# Sensor_Board.net
KiCad netlist of a schematic drawn in Altium Designer
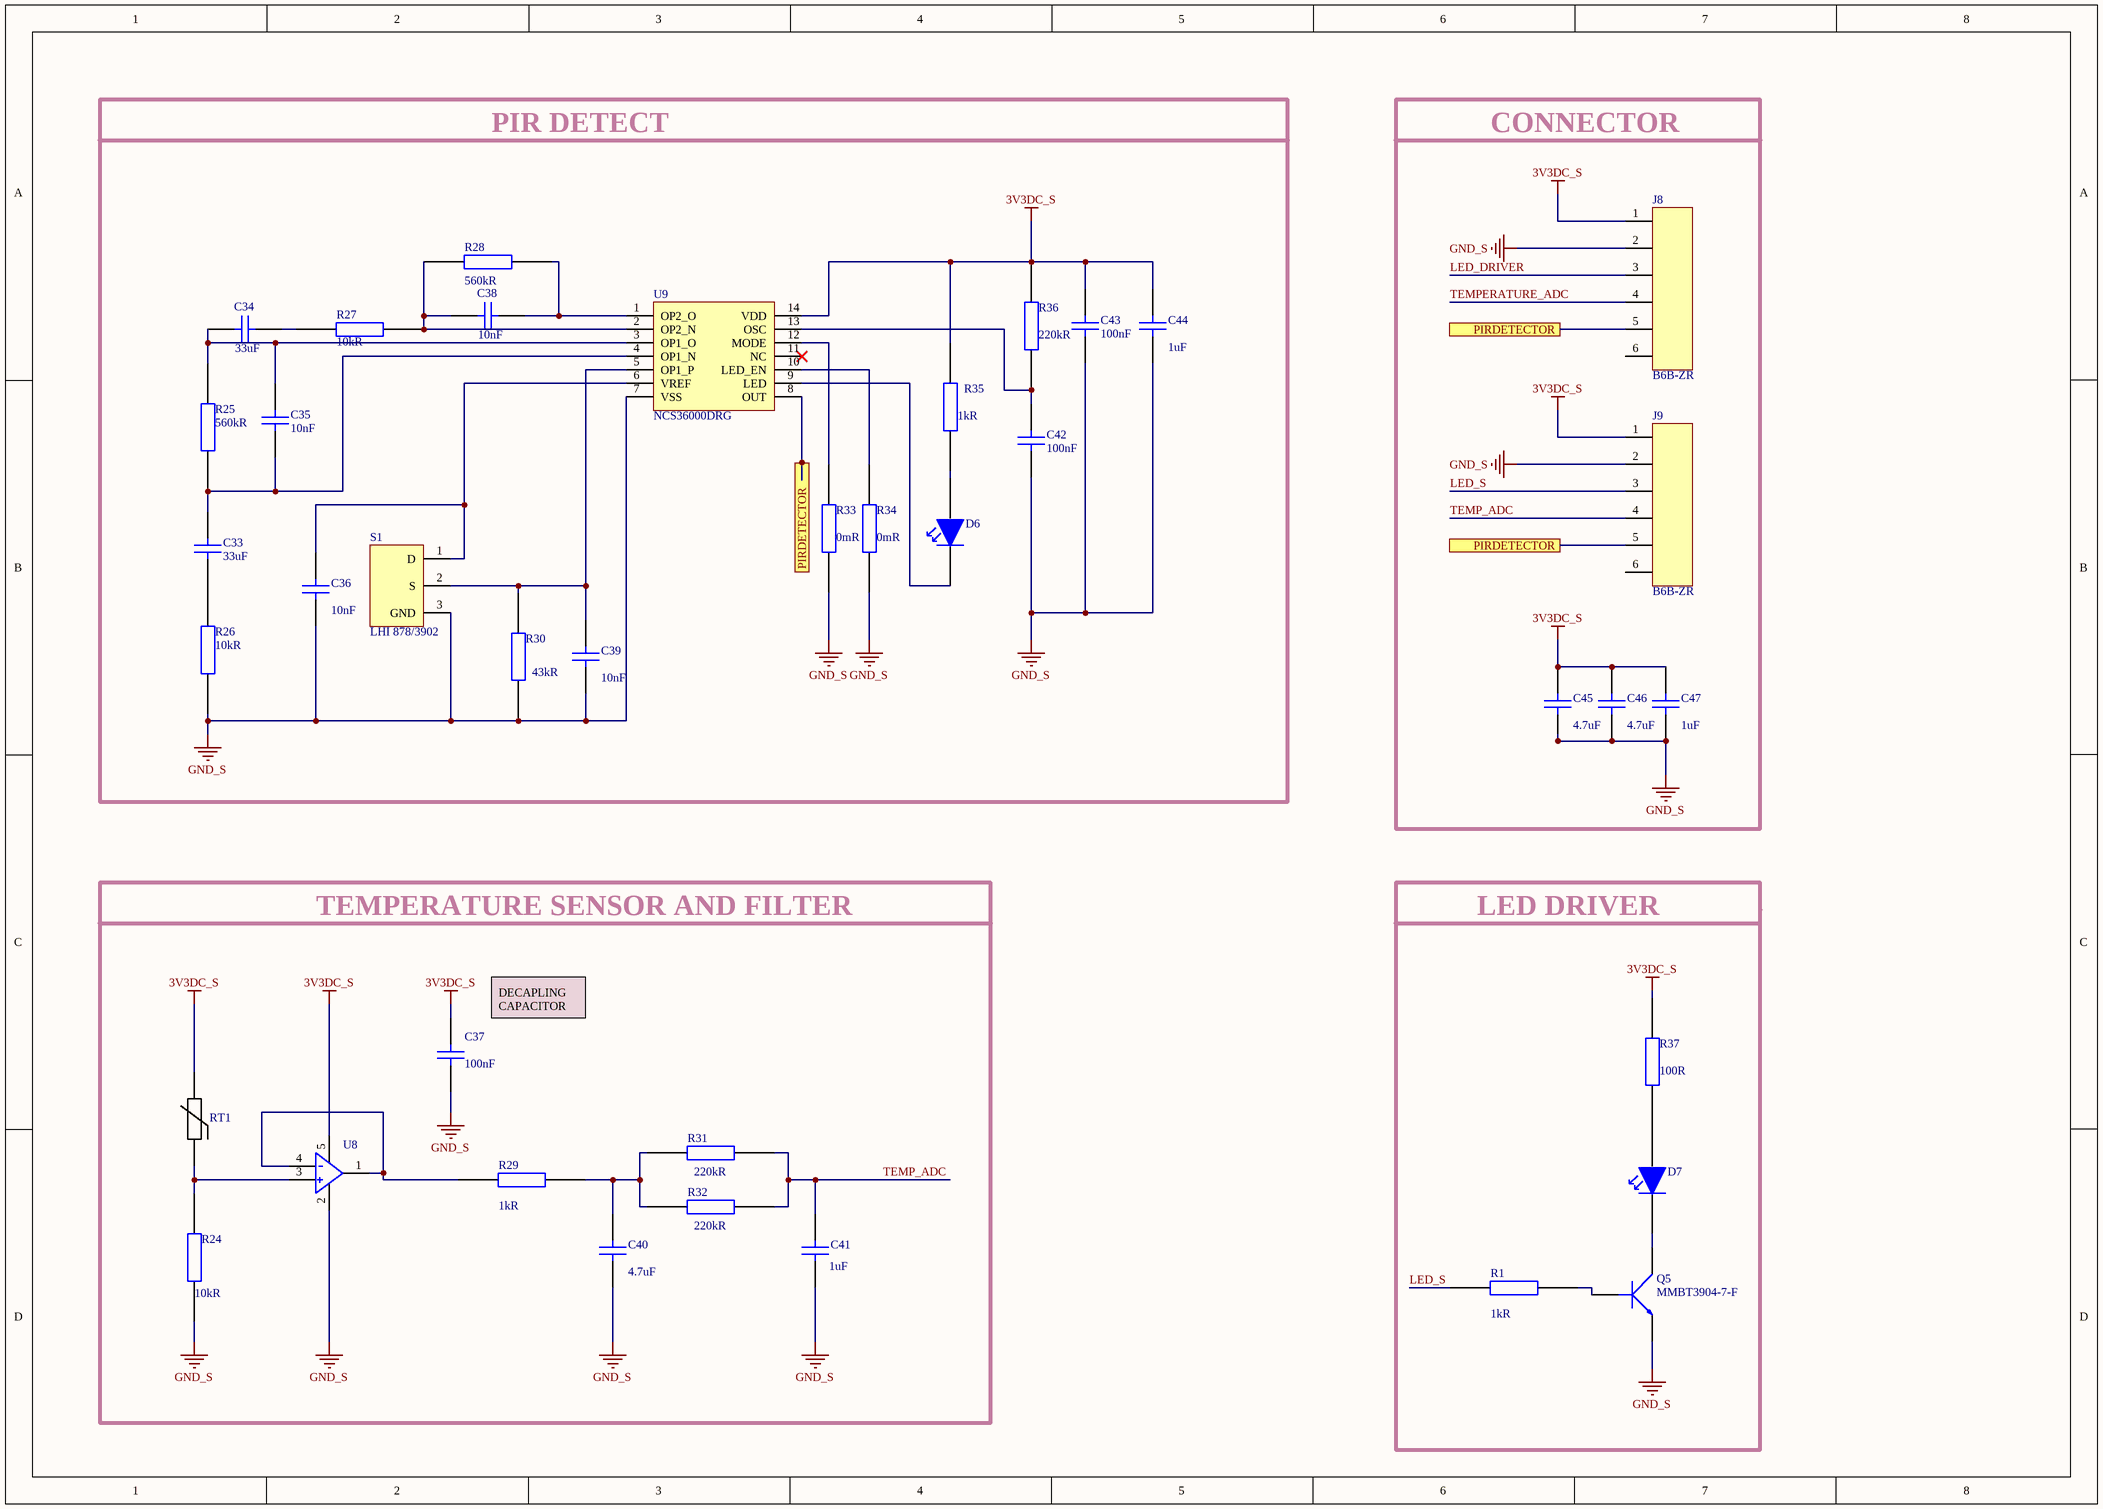
[diagram p0: Sensor Board.SchDoc]

(export (version "E")
  (design (tool "Eeschema 10.0.6"))
  (components
    (comp (ref "C33")
      (value "33uF")
      (footprint "CAP_1206")
      (description "Multilayer Ceramic Capacitor, 33 uF, 25 V, ± 20%, 1206")
      (fields
        (field (name "MANUFACTURER") "TDK")
        (field (name "MANUFACTURER PART NUMBER") "C3216X5R1E336M160AC")
        (field (name "DESIGNED BY") "Selenay")
      )
      (libsource (lib "LIBRARY1") (part "CAP CER 33uF 1206"))
    )
    (comp (ref "C34")
      (value "33uF")
      (footprint "CAP_1206")
      (description "Multilayer Ceramic Capacitor, 33 uF, 25 V, ± 20%, 1206")
      (fields
        (field (name "MANUFACTURER") "TDK")
        (field (name "MANUFACTURER PART NUMBER") "C3216X5R1E336M160AC")
        (field (name "DESIGNED BY") "Selenay")
      )
      (libsource (lib "LIBRARY1") (part "CAP CER 33uF 1206"))
    )
    (comp (ref "C35")
      (value "0603B103K160CT")
      (footprint "CAP_0603")
      (description "0603 16V X7R .01uF 10% multilayer ceramic capacitor")
      (fields
        (field (name "MANUFACTURER") "Walsin Technologies")
        (field (name "VALUES") "10nF")
        (field (name "DESIGNED BY") "Selenay")
      )
      (libsource (lib "LIBRARY1") (part "CAP CER 10nF 0603"))
    )
    (comp (ref "C36")
      (value "0603B103K160CT")
      (footprint "CAP_0603")
      (description "0603 16V X7R .01uF 10% multilayer ceramic capacitor")
      (fields
        (field (name "MANUFACTURER") "Walsin Technologies")
        (field (name "VALUES") "10nF")
        (field (name "DESIGNED BY") "Selenay")
      )
      (libsource (lib "LIBRARY1") (part "CAP CER 10nF 0603"))
    )
    (comp (ref "C37")
      (value "100nF")
      (footprint "CAP_0603")
      (description "Multilayer Ceramic Capacitor, 0.1 uF, 50 V, ± 10%, X7R, 0603 [1608 Metric]")
      (fields
        (field (name "MANUFACTURER") "KEMET")
        (field (name "MANUFACTURER PART NUMBER") "C0603C104K5RACTU")
        (field (name "DESIGNED BY") "Selenay")
      )
      (libsource (lib "LIBRARY1") (part "CAP CER 100nF 0603"))
    )
    (comp (ref "C38")
      (value "0603B103K160CT")
      (footprint "CAP_0603")
      (description "0603 16V X7R .01uF 10% multilayer ceramic capacitor")
      (fields
        (field (name "MANUFACTURER") "Walsin Technologies")
        (field (name "VALUES") "10nF")
        (field (name "DESIGNED BY") "Selenay")
      )
      (libsource (lib "LIBRARY1") (part "CAP CER 10nF 0603"))
    )
    (comp (ref "C39")
      (value "0603B103K160CT")
      (footprint "CAP_0603")
      (description "0603 16V X7R .01uF 10% multilayer ceramic capacitor")
      (fields
        (field (name "MANUFACTURER") "Walsin Technologies")
        (field (name "VALUES") "10nF")
        (field (name "DESIGNED BY") "Selenay")
      )
      (libsource (lib "LIBRARY1") (part "CAP CER 10nF 0603"))
    )
    (comp (ref "C40")
      (value "4.7uF")
      (footprint "CAP_0805")
      (description "Multilayer Ceramic Capacitor, 4.7 uF, 25 V, ± 10%")
      (fields
        (field (name "MANUFACTURER") "Samsung")
        (field (name "MANUFACTURER PART NUMBER") "CL21A475KAQNNNE")
        (field (name "DESIGNED BY") "Selenay")
      )
      (libsource (lib "LIBRARY1") (part "CAP CER 4.7uF 0805"))
    )
    (comp (ref "C41")
      (value "1uF")
      (footprint "CAP_0805")
      (description "Multilayer Ceramic Capacitor, 1 uF, 50 V, ± 10%, X7R, 0805 [2012 Metric]")
      (fields
        (field (name "MANUFACTURER") "Samsung")
        (field (name "MANUFACTURER PART NUMBER") "CL21B105KBFNNNE")
        (field (name "DESIGNED BY") "Selenay")
      )
      (libsource (lib "LIBRARY1") (part "CAP CER 1uF 0805"))
    )
    (comp (ref "C42")
      (value "100nF")
      (footprint "CAP_0603")
      (description "Multilayer Ceramic Capacitor, 0.1 uF, 50 V, ± 10%, X7R, 0603 [1608 Metric]")
      (fields
        (field (name "MANUFACTURER") "KEMET")
        (field (name "MANUFACTURER PART NUMBER") "C0603C104K5RACTU")
        (field (name "DESIGNED BY") "Selenay")
      )
      (libsource (lib "LIBRARY1") (part "CAP CER 100nF 0603"))
    )
    (comp (ref "C43")
      (value "100nF")
      (footprint "CAP_0603")
      (description "Multilayer Ceramic Capacitor, 0.1 uF, 50 V, ± 10%, X7R, 0603 [1608 Metric]")
      (fields
        (field (name "MANUFACTURER") "KEMET")
        (field (name "MANUFACTURER PART NUMBER") "C0603C104K5RACTU")
        (field (name "DESIGNED BY") "Selenay")
      )
      (libsource (lib "LIBRARY1") (part "CAP CER 100nF 0603"))
    )
    (comp (ref "C44")
      (value "1uF")
      (footprint "CAP_0805")
      (description "Multilayer Ceramic Capacitor, 1 uF, 50 V, ± 10%, X7R, 0805 [2012 Metric]")
      (fields
        (field (name "MANUFACTURER") "Samsung")
        (field (name "MANUFACTURER PART NUMBER") "CL21B105KBFNNNE")
        (field (name "DESIGNED BY") "Selenay")
      )
      (libsource (lib "LIBRARY1") (part "CAP CER 1uF 0805"))
    )
    (comp (ref "C45")
      (value "4.7uF")
      (footprint "CAP_0805")
      (description "Multilayer Ceramic Capacitor, 4.7 uF, 25 V, ± 10%")
      (fields
        (field (name "MANUFACTURER") "Samsung")
        (field (name "MANUFACTURER PART NUMBER") "CL21A475KAQNNNE")
        (field (name "DESIGNED BY") "Selenay")
      )
      (libsource (lib "LIBRARY1") (part "CAP CER 4.7uF 0805"))
    )
    (comp (ref "C46")
      (value "4.7uF")
      (footprint "CAP_0805")
      (description "Multilayer Ceramic Capacitor, 4.7 uF, 25 V, ± 10%")
      (fields
        (field (name "MANUFACTURER") "Samsung")
        (field (name "MANUFACTURER PART NUMBER") "CL21A475KAQNNNE")
        (field (name "DESIGNED BY") "Selenay")
      )
      (libsource (lib "LIBRARY1") (part "CAP CER 4.7uF 0805"))
    )
    (comp (ref "C47")
      (value "1uF")
      (footprint "CAP_0805")
      (description "Multilayer Ceramic Capacitor, 1 uF, 50 V, ± 10%, X7R, 0805 [2012 Metric]")
      (fields
        (field (name "MANUFACTURER") "Samsung")
        (field (name "MANUFACTURER PART NUMBER") "CL21B105KBFNNNE")
        (field (name "DESIGNED BY") "Selenay")
      )
      (libsource (lib "LIBRARY1") (part "CAP CER 1uF 0805"))
    )
    (comp (ref "D6")
      (value "LTST-C171GKT")
      (footprint "LED_GREEN_0805")
      (description "LED Low-Power Uni-Color Green 565nm 2.1V 2-Pin Chip LED T/R")
      (fields (field (name "MANUFACTURER") "Vishay Lite-On"))
      (libsource (lib "LIBRARY1") (part "LED GREEN 0805"))
    )
    (comp (ref "D7")
      (value "LH R974-LP-1-0-20-R18")
      (footprint "LED_RED_0805")
      (fields (field (name "DESIGNED BY") "Selenay"))
      (libsource (lib "LIBRARY1") (part "LED RED 0805"))
    )
    (comp (ref "J8")
      (value "B6B-ZR")
      (footprint "B6B-ZR")
      (description "Conn Shrouded Header (4 Sides) HDR 6 POS 1.5mm Solder ST Top Entry SMD T/R")
      (fields
        (field (name "MANUFACTURER") "Wurth Electronics")
        (field (name "MANUFACTURER PART NUMBER") "64800611622")
      )
      (libsource (lib "LIBRARY1") (part "64800611622_CONN_6PIN"))
    )
    (comp (ref "J9")
      (value "B6B-ZR")
      (footprint "B6B-ZR")
      (description "Conn Shrouded Header (4 Sides) HDR 6 POS 1.5mm Solder ST Top Entry SMD T/R")
      (fields
        (field (name "MANUFACTURER") "Wurth Electronics")
        (field (name "MANUFACTURER PART NUMBER") "64800611622")
      )
      (libsource (lib "LIBRARY1") (part "64800611622_CONN_6PIN"))
    )
    (comp (ref "Q5")
      (value "MMBT3904-7-F")
      (footprint "SOT-23F")
      (description "Transistor General Purpose BJT NPN 40 Volt 0.2A Automotive 3-Pin SOT-23")
      (fields (field (name "MANUFACTURER") "Diodes Zetex") (field (name "DESIGNED BY") "Selenay"))
      (libsource (lib "LIBRARY1") (part "MMBT3904-7-F"))
    )
    (comp (ref "R1")
      (value "1kR")
      (footprint "RES_0603")
      (description "SMD Chip Resistor, 1 kOhm, ± 1%, 100 mW, 0603 [1608 Metric], Thick Film, General Purpose")
      (fields
        (field (name "MANUFACTURER") "Yageo")
        (field (name "MANUFACTURER PART NUMBER") "RC0603FR-071KL")
        (field (name "DESIGNED BY") "Selenay")
      )
      (libsource (lib "LIBRARY1") (part "RES 1K OHM 0603"))
    )
    (comp (ref "R24")
      (value "10kR")
      (footprint "RES_0603")
      (description "Res Thick Film 0603 10K Ohm 5% 1/10W ±100ppm/°C Molded SMD SMD Paper T/R")
      (fields
        (field (name "MANUFACTURER") "Stackpole Electronics")
        (field (name "MANUFACTURER PART NUMBER") "RMCF0603JT10K0")
        (field (name "DESIGNED BY") "Selenay")
      )
      (libsource (lib "LIBRARY1") (part "RES 10K OHM 0603"))
    )
    (comp (ref "R25")
      (value "560kR")
      (footprint "RES_0603")
      (description "SMD Chip Resistor, 560 kOhm, ± 5%, 100 mW, 0603 [1608 Metric], Thick Film, General Purpose")
      (fields
        (field (name "MANUFACTURER") "Yageo")
        (field (name "MANUFACTURER PART NUMBER") "RC0603JR-07560KL")
        (field (name "DESIGNED BY") "Selenay")
      )
      (libsource (lib "LIBRARY1") (part "RES 560K OHM 0603"))
    )
    (comp (ref "R26")
      (value "10kR")
      (footprint "RES_0603")
      (description "Res Thick Film 0603 10K Ohm 5% 1/10W ±100ppm/°C Molded SMD SMD Paper T/R")
      (fields
        (field (name "MANUFACTURER") "Stackpole Electronics")
        (field (name "MANUFACTURER PART NUMBER") "RMCF0603JT10K0")
        (field (name "DESIGNED BY") "Selenay")
      )
      (libsource (lib "") (part "RES 10K OHM 0603_1"))
    )
    (comp (ref "R27")
      (value "10kR")
      (footprint "RES_0603")
      (description "Res Thick Film 0603 10K Ohm 5% 1/10W ±100ppm/°C Molded SMD SMD Paper T/R")
      (fields
        (field (name "MANUFACTURER") "Stackpole Electronics")
        (field (name "MANUFACTURER PART NUMBER") "RMCF0603JT10K0")
        (field (name "DESIGNED BY") "Selenay")
      )
      (libsource (lib "") (part "RES 10K OHM 0603_2"))
    )
    (comp (ref "R28")
      (value "560kR")
      (footprint "RES_0603")
      (description "SMD Chip Resistor, 560 kOhm, ± 5%, 100 mW, 0603 [1608 Metric], Thick Film, General Purpose")
      (fields
        (field (name "MANUFACTURER") "Yageo")
        (field (name "MANUFACTURER PART NUMBER") "RC0603JR-07560KL")
        (field (name "DESIGNED BY") "Selenay")
      )
      (libsource (lib "") (part "RES 560K OHM 0603_1"))
    )
    (comp (ref "R29")
      (value "1kR")
      (footprint "RES_0603")
      (description "SMD Chip Resistor, 1 kOhm, ± 1%, 100 mW, 0603 [1608 Metric], Thick Film, General Purpose")
      (fields
        (field (name "MANUFACTURER") "Yageo")
        (field (name "MANUFACTURER PART NUMBER") "RC0603FR-071KL")
        (field (name "DESIGNED BY") "Selenay")
      )
      (libsource (lib "LIBRARY1") (part "RES 1K OHM 0603"))
    )
    (comp (ref "R30")
      (value "RC0603JR-0743KL")
      (footprint "RES_0603")
      (description "Res Thick Film 0603 43K Ohm 5% 0.1W(1/10W)")
      (fields
        (field (name "MANUFACTURER") "Yageo")
        (field (name "VALUES") "43kR")
        (field (name "DESIGNED BY") "Selenay")
      )
      (libsource (lib "LIBRARY1") (part "RES 43K OHM 0603"))
    )
    (comp (ref "R31")
      (value "RC0603JR-07220KL")
      (footprint "RES_0603")
      (description "SMD Chip Resistor, 220 kOhm, ± 5%, 100 mW, 0603")
      (fields
        (field (name "MANUFACTURER") "Yageo")
        (field (name "VALUES") "220kR")
        (field (name "DESIGNED BY") "Selenay")
      )
      (libsource (lib "LIBRARY1") (part "RES 220K OHM 0603"))
    )
    (comp (ref "R32")
      (value "RC0603JR-07220KL")
      (footprint "RES_0603")
      (description "SMD Chip Resistor, 220 kOhm, ± 5%, 100 mW, 0603")
      (fields
        (field (name "MANUFACTURER") "Yageo")
        (field (name "VALUES") "220kR")
        (field (name "DESIGNED BY") "Selenay")
      )
      (libsource (lib "LIBRARY1") (part "RES 220K OHM 0603"))
    )
    (comp (ref "R33")
      (value "0mR")
      (footprint "RES_0603")
      (description "GENERAL PURPOSE CHIP RESISTOR Metal Glaze/thick Film, 0.1W, 0ohm, Surface Mount, 0603")
      (fields
        (field (name "MANUFACTURER") "Yageo")
        (field (name "MANUFACTURER PART NUMBER") "RC0603JR-070RL")
        (field (name "DESIGNED BY") "Selenay")
      )
      (libsource (lib "LIBRARY1") (part "RES 0 OHM 0603"))
    )
    (comp (ref "R34")
      (value "0mR")
      (footprint "RES_0603")
      (description "GENERAL PURPOSE CHIP RESISTOR Metal Glaze/thick Film, 0.1W, 0ohm, Surface Mount, 0603")
      (fields
        (field (name "MANUFACTURER") "Yageo")
        (field (name "MANUFACTURER PART NUMBER") "RC0603JR-070RL")
        (field (name "DESIGNED BY") "Selenay")
      )
      (libsource (lib "LIBRARY1") (part "RES 0 OHM 0603"))
    )
    (comp (ref "R35")
      (value "1kR")
      (footprint "RES_0603")
      (description "SMD Chip Resistor, 1 kOhm, ± 1%, 100 mW, 0603 [1608 Metric], Thick Film, General Purpose")
      (fields
        (field (name "MANUFACTURER") "Yageo")
        (field (name "MANUFACTURER PART NUMBER") "RC0603FR-071KL")
        (field (name "DESIGNED BY") "Selenay")
      )
      (libsource (lib "") (part "RES 1K OHM 0603_1"))
    )
    (comp (ref "R36")
      (value "RC0603JR-07220KL")
      (footprint "RES_0603")
      (description "SMD Chip Resistor, 220 kOhm, ± 5%, 100 mW, 0603")
      (fields
        (field (name "MANUFACTURER") "Yageo")
        (field (name "VALUES") "220kR")
        (field (name "DESIGNED BY") "Selenay")
      )
      (libsource (lib "") (part "RES 220K OHM 0603_1"))
    )
    (comp (ref "R37")
      (value "100R")
      (footprint "RES_0603")
      (description "SMD Chip Resistor, 100 Ohm, ± 1%, 100 mW, 0603")
      (fields
        (field (name "MANUFACTURER") "Yageo")
        (field (name "MANUFACTURER PART NUMBER") "RC0603FR-07100RL")
        (field (name "DESIGNED BY") "Selenay")
      )
      (libsource (lib "LIBRARY1") (part "RES 100 OHM 0603"))
    )
    (comp (ref "RT1")
      (value "TFPT1206L1002FM")
      (footprint "RES_1206")
      (description "Thermistor PTC 10K Ohm 1% 2-Pin 1206 Surface Mount Solder Pad T/R Automotive")
      (fields
        (field (name "MANUFACTURER") "Vishay Dale")
        (field (name "TOLERANCE") "1%")
        (field (name "DESIGNED BY") "Selenay")
      )
      (libsource (lib "LIBRARY1") (part "TFPT1206L1002FM"))
    )
    (comp (ref "S1")
      (value "LHI 878/3902")
      (footprint "LHI 878")
      (description "SENSOR PYRO DETECTOR DUAL MOTION")
      (fields (field (name "DESIGNED BY") "Selenay"))
      (libsource (lib "LIBRARY1") (part "LHI 878/3902"))
    )
    (comp (ref "U8")
      (value "OPA314AIDBVR")
      (footprint "SOT23_5")
      (description "IC OPAMP GP 3MHZ RRO SOT23-5")
      (fields (field (name "MANUFACTURER") "Texas Instruments") (field (name "DESIGNED BY") "Selenay"))
      (libsource (lib "LIBRARY1") (part "OPA314"))
    )
    (comp (ref "U9")
      (value "NCS36000DRG")
      (footprint "SOIC14")
      (description "PIR CONTROLLER  NCS36000 Series Single 5.75V Passive Infrared Detector Controller (PIR) -SOIC-14")
      (fields (field (name "MANUFACTURER") "ON Semiconductor") (field (name "DESIGNED BY") "Selenay"))
      (libsource (lib "LIBRARY1") (part "NCS36000"))
    )
  )
  (nets
    (net (code "1") (name "/LED_DRIVER") (class "Default") (node (ref "J8") (pin "3") (pintype "passive")))
    (net (code "2") (name "/LED_S") (class "Default")
      (node (ref "J9") (pin "3") (pintype "passive"))
      (node (ref "R1") (pin "1") (pinfunction "1_1") (pintype "passive"))
    )
    (net (code "3") (name "/PIRDETECTOR") (class "Default")
      (node (ref "J8") (pin "5") (pintype "passive"))
      (node (ref "J9") (pin "5") (pintype "passive"))
      (node (ref "U9") (pin "8") (pinfunction "OUT_8") (pintype "passive"))
    )
    (net (code "4") (name "/TEMPERATURE_ADC") (class "Default")
      (node (ref "J8") (pin "4") (pintype "passive"))
    )
    (net (code "5") (name "/TEMP_ADC") (class "Default")
      (node (ref "C41") (pin "1") (pinfunction "1_1") (pintype "passive"))
      (node (ref "J9") (pin "4") (pintype "passive"))
      (node (ref "R31") (pin "2") (pinfunction "1_2") (pintype "passive"))
      (node (ref "R32") (pin "2") (pinfunction "1_2") (pintype "passive"))
    )
    (net (code "6") (name "3V3DC_S") (class "Default")
      (node (ref "C37") (pin "2") (pinfunction "2_2") (pintype "passive"))
      (node (ref "C43") (pin "2") (pinfunction "2_2") (pintype "passive"))
      (node (ref "C44") (pin "2") (pinfunction "2_2") (pintype "passive"))
      (node (ref "C45") (pin "2") (pinfunction "2_2") (pintype "passive"))
      (node (ref "C46") (pin "2") (pinfunction "2_2") (pintype "passive"))
      (node (ref "C47") (pin "2") (pinfunction "2_2") (pintype "passive"))
      (node (ref "J8") (pin "1") (pintype "passive"))
      (node (ref "J9") (pin "1") (pintype "passive"))
      (node (ref "R35") (pin "2") (pinfunction "1_2") (pintype "passive"))
      (node (ref "R36") (pin "1") (pinfunction "1_1") (pintype "passive"))
      (node (ref "R37") (pin "2") (pinfunction "1_2") (pintype "passive"))
      (node (ref "RT1") (pin "2") (pinfunction "2_2") (pintype "passive"))
      (node (ref "U8") (pin "5") (pintype "passive"))
      (node (ref "U9") (pin "14") (pinfunction "VDD_14") (pintype "passive"))
    )
    (net (code "7") (name "GND_S") (class "Default")
      (node (ref "C36") (pin "1") (pinfunction "1_1") (pintype "passive"))
      (node (ref "C37") (pin "1") (pinfunction "1_1") (pintype "passive"))
      (node (ref "C39") (pin "1") (pinfunction "1_1") (pintype "passive"))
      (node (ref "C40") (pin "1") (pinfunction "1_1") (pintype "passive"))
      (node (ref "C41") (pin "2") (pinfunction "2_2") (pintype "passive"))
      (node (ref "C42") (pin "1") (pinfunction "1_1") (pintype "passive"))
      (node (ref "C43") (pin "1") (pinfunction "1_1") (pintype "passive"))
      (node (ref "C44") (pin "1") (pinfunction "1_1") (pintype "passive"))
      (node (ref "C45") (pin "1") (pinfunction "1_1") (pintype "passive"))
      (node (ref "C46") (pin "1") (pinfunction "1_1") (pintype "passive"))
      (node (ref "C47") (pin "1") (pinfunction "1_1") (pintype "passive"))
      (node (ref "J8") (pin "2") (pintype "passive"))
      (node (ref "J9") (pin "2") (pintype "passive"))
      (node (ref "Q5") (pin "2") (pinfunction "E_2") (pintype "passive"))
      (node (ref "R24") (pin "2") (pinfunction "1_2") (pintype "passive"))
      (node (ref "R26") (pin "1") (pinfunction "1_1") (pintype "passive"))
      (node (ref "R30") (pin "2") (pinfunction "1_2") (pintype "passive"))
      (node (ref "R33") (pin "1") (pinfunction "1_1") (pintype "passive"))
      (node (ref "R34") (pin "1") (pinfunction "1_1") (pintype "passive"))
      (node (ref "S1") (pin "3") (pinfunction "GND_3") (pintype "passive"))
      (node (ref "U8") (pin "2") (pintype "passive"))
      (node (ref "U9") (pin "7") (pinfunction "VSS_7") (pintype "passive"))
    )
    (net (code "8") (name "Net-(C33-Pad2)") (class "Default")
      (node (ref "C33") (pin "2") (pinfunction "2_2") (pintype "passive"))
      (node (ref "R26") (pin "2") (pinfunction "1_2") (pintype "passive"))
    )
    (net (code "9") (name "Net-(C34-Pad1)") (class "Default")
      (node (ref "C34") (pin "1") (pinfunction "1_1") (pintype "passive"))
      (node (ref "R27") (pin "1") (pinfunction "1_1") (pintype "passive"))
    )
    (net (code "10") (name "Net-(C40-Pad2)") (class "Default")
      (node (ref "C40") (pin "2") (pinfunction "2_2") (pintype "passive"))
      (node (ref "R29") (pin "2") (pinfunction "1_2") (pintype "passive"))
      (node (ref "R31") (pin "1") (pinfunction "1_1") (pintype "passive"))
      (node (ref "R32") (pin "1") (pinfunction "1_1") (pintype "passive"))
    )
    (net (code "11") (name "Net-(D6-Pad2)") (class "Default")
      (node (ref "D6") (pin "2") (pinfunction "2_2") (pintype "passive"))
      (node (ref "R35") (pin "1") (pinfunction "1_1") (pintype "passive"))
    )
    (net (code "12") (name "Net-(D7-Pad2)") (class "Default")
      (node (ref "D7") (pin "2") (pinfunction "2_2") (pintype "passive"))
      (node (ref "R37") (pin "1") (pinfunction "1_1") (pintype "passive"))
    )
    (net (code "13") (name "Net-(Q5-B)") (class "Default")
      (node (ref "Q5") (pin "1") (pinfunction "B_1") (pintype "passive"))
      (node (ref "R1") (pin "2") (pinfunction "1_2") (pintype "passive"))
    )
    (net (code "14") (name "Net-(Q5-C)") (class "Default")
      (node (ref "D7") (pin "1") (pinfunction "1_1") (pintype "passive"))
      (node (ref "Q5") (pin "3") (pinfunction "C_3") (pintype "passive"))
    )
    (net (code "15") (name "Net-(R24-Pad1)") (class "Default")
      (node (ref "R24") (pin "1") (pinfunction "1_1") (pintype "passive"))
      (node (ref "RT1") (pin "1") (pinfunction "1_1") (pintype "passive"))
      (node (ref "U8") (pin "3") (pintype "passive"))
    )
    (net (code "16") (name "Net-(R29-Pad1)") (class "Default")
      (node (ref "R29") (pin "1") (pinfunction "1_1") (pintype "passive"))
      (node (ref "U8") (pin "1") (pintype "passive"))
      (node (ref "U8") (pin "4") (pintype "passive"))
    )
    (net (code "17") (name "Net-(S1-D)") (class "Default")
      (node (ref "C36") (pin "2") (pinfunction "2_2") (pintype "passive"))
      (node (ref "S1") (pin "1") (pinfunction "D_1") (pintype "passive"))
      (node (ref "U9") (pin "6") (pinfunction "VREF_6") (pintype "passive"))
    )
    (net (code "18") (name "Net-(S1-S)") (class "Default")
      (node (ref "C39") (pin "2") (pinfunction "2_2") (pintype "passive"))
      (node (ref "R30") (pin "1") (pinfunction "1_1") (pintype "passive"))
      (node (ref "S1") (pin "2") (pinfunction "S_2") (pintype "passive"))
      (node (ref "U9") (pin "5") (pinfunction "OP1_P_5") (pintype "passive"))
    )
    (net (code "19") (name "Net-(U9-LED)") (class "Default")
      (node (ref "D6") (pin "1") (pinfunction "1_1") (pintype "passive"))
      (node (ref "U9") (pin "9") (pinfunction "LED_9") (pintype "passive"))
    )
    (net (code "20") (name "Net-(U9-LED_EN)") (class "Default")
      (node (ref "R34") (pin "2") (pinfunction "1_2") (pintype "passive"))
      (node (ref "U9") (pin "10") (pinfunction "LED_EN_10") (pintype "passive"))
    )
    (net (code "21") (name "Net-(U9-MODE)") (class "Default")
      (node (ref "R33") (pin "2") (pinfunction "1_2") (pintype "passive"))
      (node (ref "U9") (pin "12") (pinfunction "MODE_12") (pintype "passive"))
    )
    (net (code "22") (name "Net-(U9-OP1_N)") (class "Default")
      (node (ref "C33") (pin "1") (pinfunction "1_1") (pintype "passive"))
      (node (ref "C35") (pin "2") (pinfunction "2_2") (pintype "passive"))
      (node (ref "R25") (pin "1") (pinfunction "1_1") (pintype "passive"))
      (node (ref "U9") (pin "4") (pinfunction "OP1_N_4") (pintype "passive"))
    )
    (net (code "23") (name "Net-(U9-OP1_O)") (class "Default")
      (node (ref "C34") (pin "2") (pinfunction "2_2") (pintype "passive"))
      (node (ref "C35") (pin "1") (pinfunction "1_1") (pintype "passive"))
      (node (ref "R25") (pin "2") (pinfunction "1_2") (pintype "passive"))
      (node (ref "U9") (pin "3") (pinfunction "OP1_O_3") (pintype "passive"))
    )
    (net (code "24") (name "Net-(U9-OP2_N)") (class "Default")
      (node (ref "C38") (pin "1") (pinfunction "1_1") (pintype "passive"))
      (node (ref "R27") (pin "2") (pinfunction "1_2") (pintype "passive"))
      (node (ref "R28") (pin "1") (pinfunction "1_1") (pintype "passive"))
      (node (ref "U9") (pin "2") (pinfunction "OP2_N_2") (pintype "passive"))
    )
    (net (code "25") (name "Net-(U9-OP2_O)") (class "Default")
      (node (ref "C38") (pin "2") (pinfunction "2_2") (pintype "passive"))
      (node (ref "R28") (pin "2") (pinfunction "1_2") (pintype "passive"))
      (node (ref "U9") (pin "1") (pinfunction "OP2_O_1") (pintype "passive"))
    )
    (net (code "26") (name "Net-(U9-OSC)") (class "Default")
      (node (ref "C42") (pin "2") (pinfunction "2_2") (pintype "passive"))
      (node (ref "R36") (pin "2") (pinfunction "1_2") (pintype "passive"))
      (node (ref "U9") (pin "13") (pinfunction "OSC_13") (pintype "passive"))
    )
    (net (code "27") (name "unconnected-(J8-Pad6)") (class "Default")
      (node (ref "J8") (pin "6") (pintype "passive"))
    )
    (net (code "28") (name "unconnected-(J9-Pad6)") (class "Default")
      (node (ref "J9") (pin "6") (pintype "passive"))
    )
    (net (code "29") (name "unconnected-(U9-NC-Pad11)") (class "Default")
      (node (ref "U9") (pin "11") (pinfunction "NC_11") (pintype "passive+no_connect"))
    )
  )
)
